# KEY_Pad.net
KiCad netlist of a schematic drawn in Altium Designer
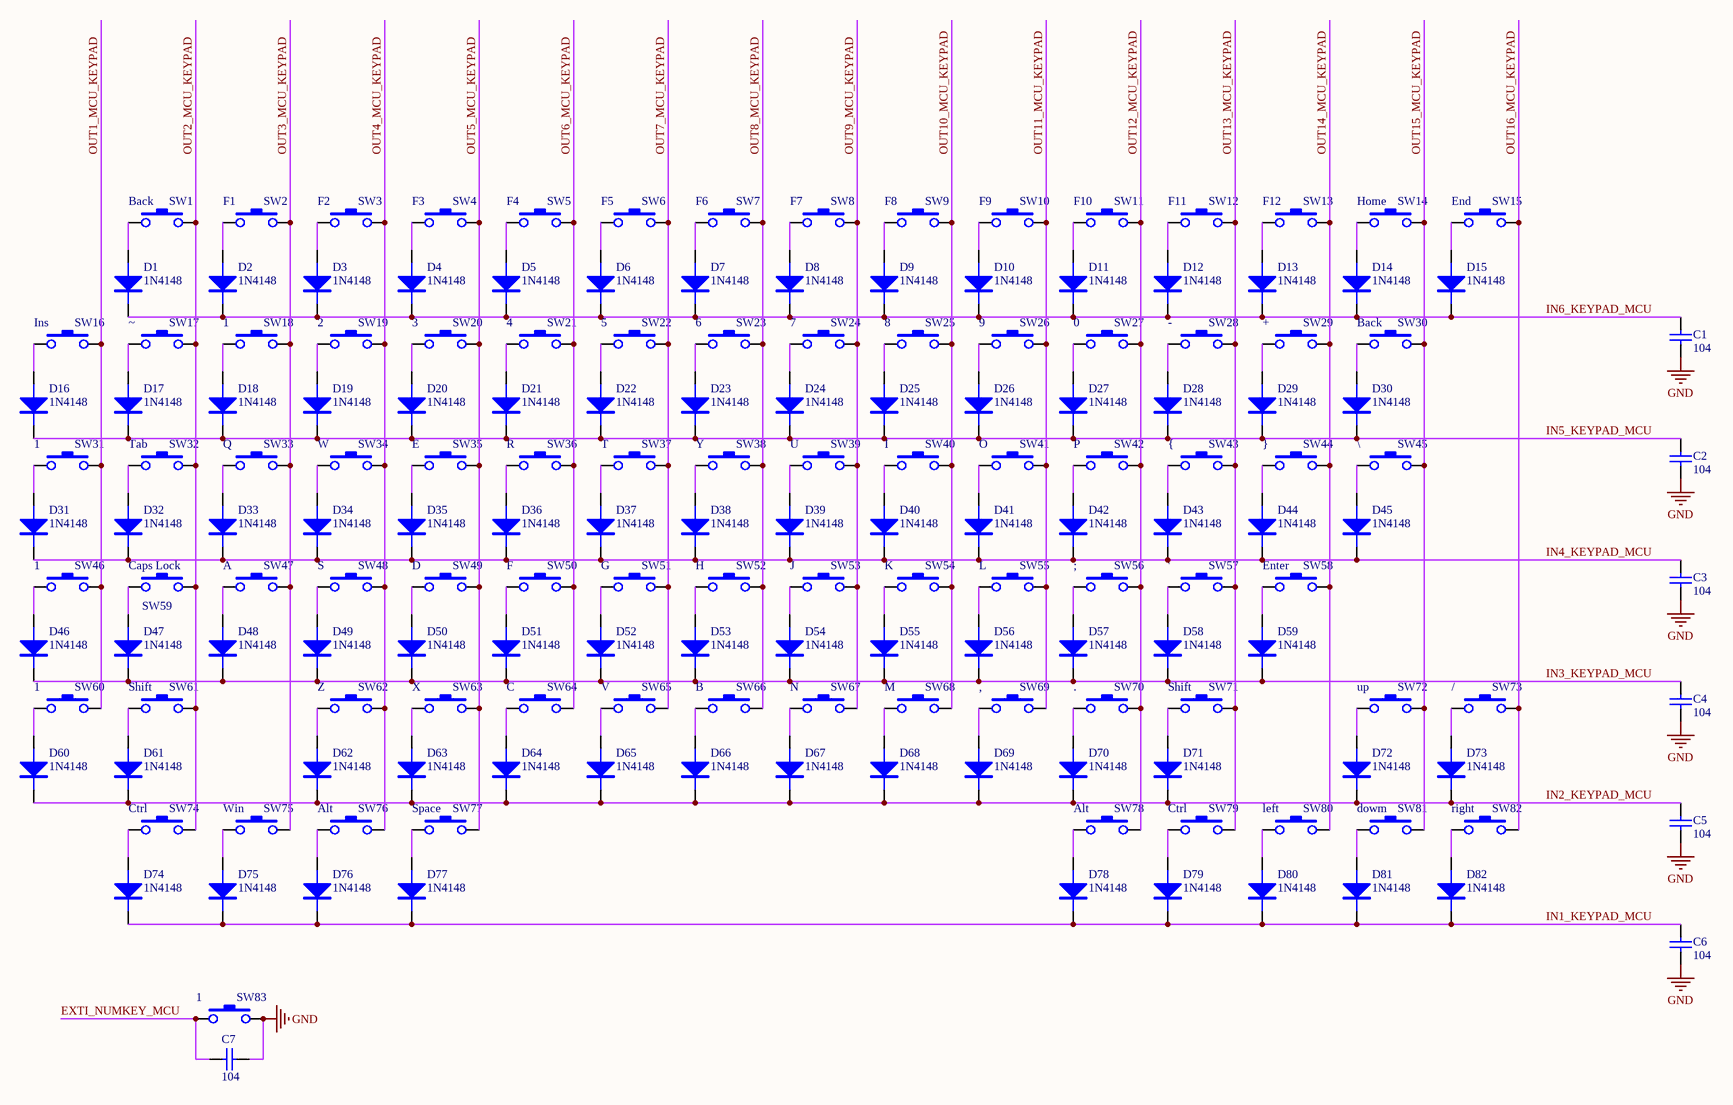
[diagram p0: KEY_Pad.SchDoc]

(export (version "E")
  (design (tool "Eeschema 10.0.6"))
  (components
    (comp (ref "C1")
      (value "104")
      (footprint "Cap-0603")
      (description "贴片陶瓷电容")
      (libsource (lib "Miscellaneous Base") (part "CAP"))
    )
    (comp (ref "C2")
      (value "104")
      (footprint "Cap-0603")
      (description "贴片陶瓷电容")
      (libsource (lib "Miscellaneous Base") (part "CAP"))
    )
    (comp (ref "C3")
      (value "104")
      (footprint "Cap-0603")
      (description "贴片陶瓷电容")
      (libsource (lib "Miscellaneous Base") (part "CAP"))
    )
    (comp (ref "C4")
      (value "104")
      (footprint "Cap-0603")
      (description "贴片陶瓷电容")
      (libsource (lib "Miscellaneous Base") (part "CAP"))
    )
    (comp (ref "C5")
      (value "104")
      (footprint "Cap-0603")
      (description "贴片陶瓷电容")
      (libsource (lib "Miscellaneous Base") (part "CAP"))
    )
    (comp (ref "C6")
      (value "104")
      (footprint "Cap-0603")
      (description "贴片陶瓷电容")
      (libsource (lib "Miscellaneous Base") (part "CAP"))
    )
    (comp (ref "C7")
      (value "104")
      (footprint "Cap-0603")
      (description "贴片陶瓷电容")
      (libsource (lib "Miscellaneous Base") (part "CAP"))
    )
    (comp (ref "D1")
      (value "1N4148")
      (footprint "SOD-523")
      (description "普通二极管")
      (libsource (lib "Miscellaneous Transistor") (part "DIODE"))
    )
    (comp (ref "D2")
      (value "1N4148")
      (footprint "SOD-523")
      (description "普通二极管")
      (libsource (lib "Miscellaneous Transistor") (part "DIODE"))
    )
    (comp (ref "D3")
      (value "1N4148")
      (footprint "SOD-523")
      (description "普通二极管")
      (libsource (lib "Miscellaneous Transistor") (part "DIODE"))
    )
    (comp (ref "D4")
      (value "1N4148")
      (footprint "SOD-523")
      (description "普通二极管")
      (libsource (lib "Miscellaneous Transistor") (part "DIODE"))
    )
    (comp (ref "D5")
      (value "1N4148")
      (footprint "SOD-523")
      (description "普通二极管")
      (libsource (lib "Miscellaneous Transistor") (part "DIODE"))
    )
    (comp (ref "D6")
      (value "1N4148")
      (footprint "SOD-523")
      (description "普通二极管")
      (libsource (lib "Miscellaneous Transistor") (part "DIODE"))
    )
    (comp (ref "D7")
      (value "1N4148")
      (footprint "SOD-523")
      (description "普通二极管")
      (libsource (lib "Miscellaneous Transistor") (part "DIODE"))
    )
    (comp (ref "D8")
      (value "1N4148")
      (footprint "SOD-523")
      (description "普通二极管")
      (libsource (lib "Miscellaneous Transistor") (part "DIODE"))
    )
    (comp (ref "D9")
      (value "1N4148")
      (footprint "SOD-523")
      (description "普通二极管")
      (libsource (lib "Miscellaneous Transistor") (part "DIODE"))
    )
    (comp (ref "D10")
      (value "1N4148")
      (footprint "SOD-523")
      (description "普通二极管")
      (libsource (lib "Miscellaneous Transistor") (part "DIODE"))
    )
    (comp (ref "D11")
      (value "1N4148")
      (footprint "SOD-523")
      (description "普通二极管")
      (libsource (lib "Miscellaneous Transistor") (part "DIODE"))
    )
    (comp (ref "D12")
      (value "1N4148")
      (footprint "SOD-523")
      (description "普通二极管")
      (libsource (lib "Miscellaneous Transistor") (part "DIODE"))
    )
    (comp (ref "D13")
      (value "1N4148")
      (footprint "SOD-523")
      (description "普通二极管")
      (libsource (lib "Miscellaneous Transistor") (part "DIODE"))
    )
    (comp (ref "D14")
      (value "1N4148")
      (footprint "SOD-523")
      (description "普通二极管")
      (libsource (lib "Miscellaneous Transistor") (part "DIODE"))
    )
    (comp (ref "D15")
      (value "1N4148")
      (footprint "SOD-523")
      (description "普通二极管")
      (libsource (lib "Miscellaneous Transistor") (part "DIODE"))
    )
    (comp (ref "D16")
      (value "1N4148")
      (footprint "SOD-523")
      (description "普通二极管")
      (libsource (lib "Miscellaneous Transistor") (part "DIODE"))
    )
    (comp (ref "D17")
      (value "1N4148")
      (footprint "SOD-523")
      (description "普通二极管")
      (libsource (lib "Miscellaneous Transistor") (part "DIODE"))
    )
    (comp (ref "D18")
      (value "1N4148")
      (footprint "SOD-523")
      (description "普通二极管")
      (libsource (lib "Miscellaneous Transistor") (part "DIODE"))
    )
    (comp (ref "D19")
      (value "1N4148")
      (footprint "SOD-523")
      (description "普通二极管")
      (libsource (lib "Miscellaneous Transistor") (part "DIODE"))
    )
    (comp (ref "D20")
      (value "1N4148")
      (footprint "SOD-523")
      (description "普通二极管")
      (libsource (lib "Miscellaneous Transistor") (part "DIODE"))
    )
    (comp (ref "D21")
      (value "1N4148")
      (footprint "SOD-523")
      (description "普通二极管")
      (libsource (lib "Miscellaneous Transistor") (part "DIODE"))
    )
    (comp (ref "D22")
      (value "1N4148")
      (footprint "SOD-523")
      (description "普通二极管")
      (libsource (lib "Miscellaneous Transistor") (part "DIODE"))
    )
    (comp (ref "D23")
      (value "1N4148")
      (footprint "SOD-523")
      (description "普通二极管")
      (libsource (lib "Miscellaneous Transistor") (part "DIODE"))
    )
    (comp (ref "D24")
      (value "1N4148")
      (footprint "SOD-523")
      (description "普通二极管")
      (libsource (lib "Miscellaneous Transistor") (part "DIODE"))
    )
    (comp (ref "D25")
      (value "1N4148")
      (footprint "SOD-523")
      (description "普通二极管")
      (libsource (lib "Miscellaneous Transistor") (part "DIODE"))
    )
    (comp (ref "D26")
      (value "1N4148")
      (footprint "SOD-523")
      (description "普通二极管")
      (libsource (lib "Miscellaneous Transistor") (part "DIODE"))
    )
    (comp (ref "D27")
      (value "1N4148")
      (footprint "SOD-523")
      (description "普通二极管")
      (libsource (lib "Miscellaneous Transistor") (part "DIODE"))
    )
    (comp (ref "D28")
      (value "1N4148")
      (footprint "SOD-523")
      (description "普通二极管")
      (libsource (lib "Miscellaneous Transistor") (part "DIODE"))
    )
    (comp (ref "D29")
      (value "1N4148")
      (footprint "SOD-523")
      (description "普通二极管")
      (libsource (lib "Miscellaneous Transistor") (part "DIODE"))
    )
    (comp (ref "D30")
      (value "1N4148")
      (footprint "SOD-523")
      (description "普通二极管")
      (libsource (lib "Miscellaneous Transistor") (part "DIODE"))
    )
    (comp (ref "D31")
      (value "1N4148")
      (footprint "SOD-523")
      (description "普通二极管")
      (libsource (lib "Miscellaneous Transistor") (part "DIODE"))
    )
    (comp (ref "D32")
      (value "1N4148")
      (footprint "SOD-523")
      (description "普通二极管")
      (libsource (lib "Miscellaneous Transistor") (part "DIODE"))
    )
    (comp (ref "D33")
      (value "1N4148")
      (footprint "SOD-523")
      (description "普通二极管")
      (libsource (lib "Miscellaneous Transistor") (part "DIODE"))
    )
    (comp (ref "D34")
      (value "1N4148")
      (footprint "SOD-523")
      (description "普通二极管")
      (libsource (lib "Miscellaneous Transistor") (part "DIODE"))
    )
    (comp (ref "D35")
      (value "1N4148")
      (footprint "SOD-523")
      (description "普通二极管")
      (libsource (lib "Miscellaneous Transistor") (part "DIODE"))
    )
    (comp (ref "D36")
      (value "1N4148")
      (footprint "SOD-523")
      (description "普通二极管")
      (libsource (lib "Miscellaneous Transistor") (part "DIODE"))
    )
    (comp (ref "D37")
      (value "1N4148")
      (footprint "SOD-523")
      (description "普通二极管")
      (libsource (lib "Miscellaneous Transistor") (part "DIODE"))
    )
    (comp (ref "D38")
      (value "1N4148")
      (footprint "SOD-523")
      (description "普通二极管")
      (libsource (lib "Miscellaneous Transistor") (part "DIODE"))
    )
    (comp (ref "D39")
      (value "1N4148")
      (footprint "SOD-523")
      (description "普通二极管")
      (libsource (lib "Miscellaneous Transistor") (part "DIODE"))
    )
    (comp (ref "D40")
      (value "1N4148")
      (footprint "SOD-523")
      (description "普通二极管")
      (libsource (lib "Miscellaneous Transistor") (part "DIODE"))
    )
    (comp (ref "D41")
      (value "1N4148")
      (footprint "SOD-523")
      (description "普通二极管")
      (libsource (lib "Miscellaneous Transistor") (part "DIODE"))
    )
    (comp (ref "D42")
      (value "1N4148")
      (footprint "SOD-523")
      (description "普通二极管")
      (libsource (lib "Miscellaneous Transistor") (part "DIODE"))
    )
    (comp (ref "D43")
      (value "1N4148")
      (footprint "SOD-523")
      (description "普通二极管")
      (libsource (lib "Miscellaneous Transistor") (part "DIODE"))
    )
    (comp (ref "D44")
      (value "1N4148")
      (footprint "SOD-523")
      (description "普通二极管")
      (libsource (lib "Miscellaneous Transistor") (part "DIODE"))
    )
    (comp (ref "D45")
      (value "1N4148")
      (footprint "SOD-523")
      (description "普通二极管")
      (libsource (lib "Miscellaneous Transistor") (part "DIODE"))
    )
    (comp (ref "D46")
      (value "1N4148")
      (footprint "SOD-523")
      (description "普通二极管")
      (libsource (lib "Miscellaneous Transistor") (part "DIODE"))
    )
    (comp (ref "D47")
      (value "1N4148")
      (footprint "SOD-523")
      (description "普通二极管")
      (libsource (lib "Miscellaneous Transistor") (part "DIODE"))
    )
    (comp (ref "D48")
      (value "1N4148")
      (footprint "SOD-523")
      (description "普通二极管")
      (libsource (lib "Miscellaneous Transistor") (part "DIODE"))
    )
    (comp (ref "D49")
      (value "1N4148")
      (footprint "SOD-523")
      (description "普通二极管")
      (libsource (lib "Miscellaneous Transistor") (part "DIODE"))
    )
    (comp (ref "D50")
      (value "1N4148")
      (footprint "SOD-523")
      (description "普通二极管")
      (libsource (lib "Miscellaneous Transistor") (part "DIODE"))
    )
    (comp (ref "D51")
      (value "1N4148")
      (footprint "SOD-523")
      (description "普通二极管")
      (libsource (lib "Miscellaneous Transistor") (part "DIODE"))
    )
    (comp (ref "D52")
      (value "1N4148")
      (footprint "SOD-523")
      (description "普通二极管")
      (libsource (lib "Miscellaneous Transistor") (part "DIODE"))
    )
    (comp (ref "D53")
      (value "1N4148")
      (footprint "SOD-523")
      (description "普通二极管")
      (libsource (lib "Miscellaneous Transistor") (part "DIODE"))
    )
    (comp (ref "D54")
      (value "1N4148")
      (footprint "SOD-523")
      (description "普通二极管")
      (libsource (lib "Miscellaneous Transistor") (part "DIODE"))
    )
    (comp (ref "D55")
      (value "1N4148")
      (footprint "SOD-523")
      (description "普通二极管")
      (libsource (lib "Miscellaneous Transistor") (part "DIODE"))
    )
    (comp (ref "D56")
      (value "1N4148")
      (footprint "SOD-523")
      (description "普通二极管")
      (libsource (lib "Miscellaneous Transistor") (part "DIODE"))
    )
    (comp (ref "D57")
      (value "1N4148")
      (footprint "SOD-523")
      (description "普通二极管")
      (libsource (lib "Miscellaneous Transistor") (part "DIODE"))
    )
    (comp (ref "D58")
      (value "1N4148")
      (footprint "SOD-523")
      (description "普通二极管")
      (libsource (lib "Miscellaneous Transistor") (part "DIODE"))
    )
    (comp (ref "D59")
      (value "1N4148")
      (footprint "SOD-523")
      (description "普通二极管")
      (libsource (lib "Miscellaneous Transistor") (part "DIODE"))
    )
    (comp (ref "D60")
      (value "1N4148")
      (footprint "SOD-523")
      (description "普通二极管")
      (libsource (lib "Miscellaneous Transistor") (part "DIODE"))
    )
    (comp (ref "D61")
      (value "1N4148")
      (footprint "SOD-523")
      (description "普通二极管")
      (libsource (lib "Miscellaneous Transistor") (part "DIODE"))
    )
    (comp (ref "D62")
      (value "1N4148")
      (footprint "SOD-523")
      (description "普通二极管")
      (libsource (lib "Miscellaneous Transistor") (part "DIODE"))
    )
    (comp (ref "D63")
      (value "1N4148")
      (footprint "SOD-523")
      (description "普通二极管")
      (libsource (lib "Miscellaneous Transistor") (part "DIODE"))
    )
    (comp (ref "D64")
      (value "1N4148")
      (footprint "SOD-523")
      (description "普通二极管")
      (libsource (lib "Miscellaneous Transistor") (part "DIODE"))
    )
    (comp (ref "D65")
      (value "1N4148")
      (footprint "SOD-523")
      (description "普通二极管")
      (libsource (lib "Miscellaneous Transistor") (part "DIODE"))
    )
    (comp (ref "D66")
      (value "1N4148")
      (footprint "SOD-523")
      (description "普通二极管")
      (libsource (lib "Miscellaneous Transistor") (part "DIODE"))
    )
    (comp (ref "D67")
      (value "1N4148")
      (footprint "SOD-523")
      (description "普通二极管")
      (libsource (lib "Miscellaneous Transistor") (part "DIODE"))
    )
    (comp (ref "D68")
      (value "1N4148")
      (footprint "SOD-523")
      (description "普通二极管")
      (libsource (lib "Miscellaneous Transistor") (part "DIODE"))
    )
    (comp (ref "D69")
      (value "1N4148")
      (footprint "SOD-523")
      (description "普通二极管")
      (libsource (lib "Miscellaneous Transistor") (part "DIODE"))
    )
    (comp (ref "D70")
      (value "1N4148")
      (footprint "SOD-523")
      (description "普通二极管")
      (libsource (lib "Miscellaneous Transistor") (part "DIODE"))
    )
    (comp (ref "D71")
      (value "1N4148")
      (footprint "SOD-523")
      (description "普通二极管")
      (libsource (lib "Miscellaneous Transistor") (part "DIODE"))
    )
    (comp (ref "D72")
      (value "1N4148")
      (footprint "SOD-523")
      (description "普通二极管")
      (libsource (lib "Miscellaneous Transistor") (part "DIODE"))
    )
    (comp (ref "D73")
      (value "1N4148")
      (footprint "SOD-523")
      (description "普通二极管")
      (libsource (lib "Miscellaneous Transistor") (part "DIODE"))
    )
    (comp (ref "D74")
      (value "1N4148")
      (footprint "SOD-523")
      (description "普通二极管")
      (libsource (lib "Miscellaneous Transistor") (part "DIODE"))
    )
    (comp (ref "D75")
      (value "1N4148")
      (footprint "SOD-523")
      (description "普通二极管")
      (libsource (lib "Miscellaneous Transistor") (part "DIODE"))
    )
    (comp (ref "D76")
      (value "1N4148")
      (footprint "SOD-523")
      (description "普通二极管")
      (libsource (lib "Miscellaneous Transistor") (part "DIODE"))
    )
    (comp (ref "D77")
      (value "1N4148")
      (footprint "SOD-523")
      (description "普通二极管")
      (libsource (lib "Miscellaneous Transistor") (part "DIODE"))
    )
    (comp (ref "D78")
      (value "1N4148")
      (footprint "SOD-523")
      (description "普通二极管")
      (libsource (lib "Miscellaneous Transistor") (part "DIODE"))
    )
    (comp (ref "D79")
      (value "1N4148")
      (footprint "SOD-523")
      (description "普通二极管")
      (libsource (lib "Miscellaneous Transistor") (part "DIODE"))
    )
    (comp (ref "D80")
      (value "1N4148")
      (footprint "SOD-523")
      (description "普通二极管")
      (libsource (lib "Miscellaneous Transistor") (part "DIODE"))
    )
    (comp (ref "D81")
      (value "1N4148")
      (footprint "SOD-523")
      (description "普通二极管")
      (libsource (lib "Miscellaneous Transistor") (part "DIODE"))
    )
    (comp (ref "D82")
      (value "1N4148")
      (footprint "SOD-523")
      (description "普通二极管")
      (libsource (lib "Miscellaneous Transistor") (part "DIODE"))
    )
    (comp (ref "SW1")
      (value "Back")
      (footprint "MX_SW-4")
      (description "with Fixation pins  1-Pole")
      (libsource (lib "KeyBoard_rebacha") (part "MX_SW-4"))
    )
    (comp (ref "SW2")
      (value "F1")
      (footprint "MX_SW-4")
      (description "with Fixation pins  1-Pole")
      (libsource (lib "KeyBoard_rebacha") (part "MX_SW-4"))
    )
    (comp (ref "SW3")
      (value "F2")
      (footprint "MX_SW-4")
      (description "with Fixation pins  1-Pole")
      (libsource (lib "KeyBoard_rebacha") (part "MX_SW-4"))
    )
    (comp (ref "SW4")
      (value "F3")
      (footprint "MX_SW-4")
      (description "with Fixation pins  1-Pole")
      (libsource (lib "KeyBoard_rebacha") (part "MX_SW-4"))
    )
    (comp (ref "SW5")
      (value "F4")
      (footprint "MX_SW-4")
      (description "with Fixation pins  1-Pole")
      (libsource (lib "KeyBoard_rebacha") (part "MX_SW-4"))
    )
    (comp (ref "SW6")
      (value "F5")
      (footprint "MX_SW-4")
      (description "with Fixation pins  1-Pole")
      (libsource (lib "KeyBoard_rebacha") (part "MX_SW-4"))
    )
    (comp (ref "SW7")
      (value "F6")
      (footprint "MX_SW-4")
      (description "with Fixation pins  1-Pole")
      (libsource (lib "KeyBoard_rebacha") (part "MX_SW-4"))
    )
    (comp (ref "SW8")
      (value "F7")
      (footprint "MX_SW-4")
      (description "with Fixation pins  1-Pole")
      (libsource (lib "KeyBoard_rebacha") (part "MX_SW-4"))
    )
    (comp (ref "SW9")
      (value "F8")
      (footprint "MX_SW-4")
      (description "with Fixation pins  1-Pole")
      (libsource (lib "KeyBoard_rebacha") (part "MX_SW-4"))
    )
    (comp (ref "SW10")
      (value "F9")
      (footprint "MX_SW-4")
      (description "with Fixation pins  1-Pole")
      (libsource (lib "KeyBoard_rebacha") (part "MX_SW-4"))
    )
    (comp (ref "SW11")
      (value "F10")
      (footprint "MX_SW-4")
      (description "with Fixation pins  1-Pole")
      (libsource (lib "KeyBoard_rebacha") (part "MX_SW-4"))
    )
    (comp (ref "SW12")
      (value "F11")
      (footprint "MX_SW-4")
      (description "with Fixation pins  1-Pole")
      (libsource (lib "KeyBoard_rebacha") (part "MX_SW-4"))
    )
    (comp (ref "SW13")
      (value "F12")
      (footprint "MX_SW-4")
      (description "with Fixation pins  1-Pole")
      (libsource (lib "KeyBoard_rebacha") (part "MX_SW-4"))
    )
    (comp (ref "SW14")
      (value "Home")
      (footprint "MX_SW-4")
      (description "with Fixation pins  1-Pole")
      (libsource (lib "KeyBoard_rebacha") (part "MX_SW-4"))
    )
    (comp (ref "SW15")
      (value "End")
      (footprint "MX_SW-4")
      (description "with Fixation pins  1-Pole")
      (libsource (lib "KeyBoard_rebacha") (part "MX_SW-4"))
    )
    (comp (ref "SW16")
      (value "Ins")
      (footprint "MX_SW-4")
      (description "with Fixation pins  1-Pole")
      (libsource (lib "KeyBoard_rebacha") (part "MX_SW-4"))
    )
    (comp (ref "SW17")
      (value "~")
      (footprint "MX_SW-4")
      (description "with Fixation pins  1-Pole")
      (libsource (lib "KeyBoard_rebacha") (part "MX_SW-4"))
    )
    (comp (ref "SW18")
      (value "1")
      (footprint "MX_SW-4")
      (description "with Fixation pins  1-Pole")
      (libsource (lib "KeyBoard_rebacha") (part "MX_SW-4"))
    )
    (comp (ref "SW19")
      (value "2")
      (footprint "MX_SW-4")
      (description "with Fixation pins  1-Pole")
      (libsource (lib "KeyBoard_rebacha") (part "MX_SW-4"))
    )
    (comp (ref "SW20")
      (value "3")
      (footprint "MX_SW-4")
      (description "with Fixation pins  1-Pole")
      (libsource (lib "KeyBoard_rebacha") (part "MX_SW-4"))
    )
    (comp (ref "SW21")
      (value "4")
      (footprint "MX_SW-4")
      (description "with Fixation pins  1-Pole")
      (libsource (lib "KeyBoard_rebacha") (part "MX_SW-4"))
    )
    (comp (ref "SW22")
      (value "5")
      (footprint "MX_SW-4")
      (description "with Fixation pins  1-Pole")
      (libsource (lib "KeyBoard_rebacha") (part "MX_SW-4"))
    )
    (comp (ref "SW23")
      (value "6")
      (footprint "MX_SW-4")
      (description "with Fixation pins  1-Pole")
      (libsource (lib "KeyBoard_rebacha") (part "MX_SW-4"))
    )
    (comp (ref "SW24")
      (value "7")
      (footprint "MX_SW-4")
      (description "with Fixation pins  1-Pole")
      (libsource (lib "KeyBoard_rebacha") (part "MX_SW-4"))
    )
    (comp (ref "SW25")
      (value "8")
      (footprint "MX_SW-4")
      (description "with Fixation pins  1-Pole")
      (libsource (lib "KeyBoard_rebacha") (part "MX_SW-4"))
    )
    (comp (ref "SW26")
      (value "9")
      (footprint "MX_SW-4")
      (description "with Fixation pins  1-Pole")
      (libsource (lib "KeyBoard_rebacha") (part "MX_SW-4"))
    )
    (comp (ref "SW27")
      (value "0")
      (footprint "MX_SW-4")
      (description "with Fixation pins  1-Pole")
      (libsource (lib "KeyBoard_rebacha") (part "MX_SW-4"))
    )
    (comp (ref "SW28")
      (value "-")
      (footprint "MX_SW-4")
      (description "with Fixation pins  1-Pole")
      (libsource (lib "KeyBoard_rebacha") (part "MX_SW-4"))
    )
    (comp (ref "SW29")
      (value "+")
      (footprint "MX_SW-4")
      (description "with Fixation pins  1-Pole")
      (libsource (lib "KeyBoard_rebacha") (part "MX_SW-4"))
    )
    (comp (ref "SW30")
      (value "Back")
      (footprint "MX_SW-4")
      (description "with Fixation pins  1-Pole")
      (libsource (lib "KeyBoard_rebacha") (part "MX_SW-4"))
    )
    (comp (ref "SW31")
      (value "1")
      (footprint "MX_SW-4")
      (description "with Fixation pins  1-Pole")
      (libsource (lib "KeyBoard_rebacha") (part "MX_SW-4"))
    )
    (comp (ref "SW32")
      (value "Tab")
      (footprint "MX_SW-4")
      (description "with Fixation pins  1-Pole")
      (libsource (lib "KeyBoard_rebacha") (part "MX_SW-4"))
    )
    (comp (ref "SW33")
      (value "Q")
      (footprint "MX_SW-4")
      (description "with Fixation pins  1-Pole")
      (libsource (lib "KeyBoard_rebacha") (part "MX_SW-4"))
    )
    (comp (ref "SW34")
      (value "W")
      (footprint "MX_SW-4")
      (description "with Fixation pins  1-Pole")
      (libsource (lib "KeyBoard_rebacha") (part "MX_SW-4"))
    )
    (comp (ref "SW35")
      (value "E")
      (footprint "MX_SW-4")
      (description "with Fixation pins  1-Pole")
      (libsource (lib "KeyBoard_rebacha") (part "MX_SW-4"))
    )
    (comp (ref "SW36")
      (value "R")
      (footprint "MX_SW-4")
      (description "with Fixation pins  1-Pole")
      (libsource (lib "KeyBoard_rebacha") (part "MX_SW-4"))
    )
    (comp (ref "SW37")
      (value "T")
      (footprint "MX_SW-4")
      (description "with Fixation pins  1-Pole")
      (libsource (lib "KeyBoard_rebacha") (part "MX_SW-4"))
    )
    (comp (ref "SW38")
      (value "Y")
      (footprint "MX_SW-4")
      (description "with Fixation pins  1-Pole")
      (libsource (lib "KeyBoard_rebacha") (part "MX_SW-4"))
    )
    (comp (ref "SW39")
      (value "U")
      (footprint "MX_SW-4")
      (description "with Fixation pins  1-Pole")
      (libsource (lib "KeyBoard_rebacha") (part "MX_SW-4"))
    )
    (comp (ref "SW40")
      (value "I")
      (footprint "MX_SW-4")
      (description "with Fixation pins  1-Pole")
      (libsource (lib "KeyBoard_rebacha") (part "MX_SW-4"))
    )
    (comp (ref "SW41")
      (value "O")
      (footprint "MX_SW-4")
      (description "with Fixation pins  1-Pole")
      (libsource (lib "KeyBoard_rebacha") (part "MX_SW-4"))
    )
    (comp (ref "SW42")
      (value "P")
      (footprint "MX_SW-4")
      (description "with Fixation pins  1-Pole")
      (libsource (lib "KeyBoard_rebacha") (part "MX_SW-4"))
    )
    (comp (ref "SW43")
      (value "{")
      (footprint "MX_SW-4")
      (description "with Fixation pins  1-Pole")
      (libsource (lib "KeyBoard_rebacha") (part "MX_SW-4"))
    )
    (comp (ref "SW44")
      (value "}")
      (footprint "MX_SW-4")
      (description "with Fixation pins  1-Pole")
      (libsource (lib "KeyBoard_rebacha") (part "MX_SW-4"))
    )
    (comp (ref "SW45")
      (value "~")
      (footprint "MX_SW-4")
      (description "with Fixation pins  1-Pole")
      (libsource (lib "KeyBoard_rebacha") (part "MX_SW-4"))
    )
    (comp (ref "SW46")
      (value "1")
      (footprint "MX_SW-4")
      (description "with Fixation pins  1-Pole")
      (libsource (lib "KeyBoard_rebacha") (part "MX_SW-4"))
    )
    (comp (ref "SW47")
      (value "A")
      (footprint "MX_SW-4")
      (description "with Fixation pins  1-Pole")
      (libsource (lib "KeyBoard_rebacha") (part "MX_SW-4"))
    )
    (comp (ref "SW48")
      (value "S")
      (footprint "MX_SW-4")
      (description "with Fixation pins  1-Pole")
      (libsource (lib "KeyBoard_rebacha") (part "MX_SW-4"))
    )
    (comp (ref "SW49")
      (value "D")
      (footprint "MX_SW-4")
      (description "with Fixation pins  1-Pole")
      (libsource (lib "KeyBoard_rebacha") (part "MX_SW-4"))
    )
    (comp (ref "SW50")
      (value "F")
      (footprint "MX_SW-4")
      (description "with Fixation pins  1-Pole")
      (libsource (lib "KeyBoard_rebacha") (part "MX_SW-4"))
    )
    (comp (ref "SW51")
      (value "G")
      (footprint "MX_SW-4")
      (description "with Fixation pins  1-Pole")
      (libsource (lib "KeyBoard_rebacha") (part "MX_SW-4"))
    )
    (comp (ref "SW52")
      (value "H")
      (footprint "MX_SW-4")
      (description "with Fixation pins  1-Pole")
      (libsource (lib "KeyBoard_rebacha") (part "MX_SW-4"))
    )
    (comp (ref "SW53")
      (value "J")
      (footprint "MX_SW-4")
      (description "with Fixation pins  1-Pole")
      (libsource (lib "KeyBoard_rebacha") (part "MX_SW-4"))
    )
    (comp (ref "SW54")
      (value "K")
      (footprint "MX_SW-4")
      (description "with Fixation pins  1-Pole")
      (libsource (lib "KeyBoard_rebacha") (part "MX_SW-4"))
    )
    (comp (ref "SW55")
      (value "L")
      (footprint "MX_SW-4")
      (description "with Fixation pins  1-Pole")
      (libsource (lib "KeyBoard_rebacha") (part "MX_SW-4"))
    )
    (comp (ref "SW56")
      (value ";")
      (footprint "MX_SW-4")
      (description "with Fixation pins  1-Pole")
      (libsource (lib "KeyBoard_rebacha") (part "MX_SW-4"))
    )
    (comp (ref "SW57")
      (value "'")
      (footprint "MX_SW-4")
      (description "with Fixation pins  1-Pole")
      (libsource (lib "KeyBoard_rebacha") (part "MX_SW-4"))
    )
    (comp (ref "SW58")
      (value "Enter")
      (footprint "MX_SW-4")
      (description "with Fixation pins  1-Pole")
      (libsource (lib "KeyBoard_rebacha") (part "MX_SW-4"))
    )
    (comp (ref "SW59")
      (value "Caps Lock")
      (footprint "MX_SW-4")
      (description "with Fixation pins  1-Pole")
      (libsource (lib "KeyBoard_rebacha") (part "MX_SW-4"))
    )
    (comp (ref "SW60")
      (value "1")
      (footprint "MX_SW-4")
      (description "with Fixation pins  1-Pole")
      (libsource (lib "KeyBoard_rebacha") (part "MX_SW-4"))
    )
    (comp (ref "SW61")
      (value "Shift")
      (footprint "MX_SW-4")
      (description "with Fixation pins  1-Pole")
      (libsource (lib "KeyBoard_rebacha") (part "MX_SW-4"))
    )
    (comp (ref "SW62")
      (value "Z")
      (footprint "MX_SW-4")
      (description "with Fixation pins  1-Pole")
      (libsource (lib "KeyBoard_rebacha") (part "MX_SW-4"))
    )
    (comp (ref "SW63")
      (value "X")
      (footprint "MX_SW-4")
      (description "with Fixation pins  1-Pole")
      (libsource (lib "KeyBoard_rebacha") (part "MX_SW-4"))
    )
    (comp (ref "SW64")
      (value "C")
      (footprint "MX_SW-4")
      (description "with Fixation pins  1-Pole")
      (libsource (lib "KeyBoard_rebacha") (part "MX_SW-4"))
    )
    (comp (ref "SW65")
      (value "V")
      (footprint "MX_SW-4")
      (description "with Fixation pins  1-Pole")
      (libsource (lib "KeyBoard_rebacha") (part "MX_SW-4"))
    )
    (comp (ref "SW66")
      (value "B")
      (footprint "MX_SW-4")
      (description "with Fixation pins  1-Pole")
      (libsource (lib "KeyBoard_rebacha") (part "MX_SW-4"))
    )
    (comp (ref "SW67")
      (value "N")
      (footprint "MX_SW-4")
      (description "with Fixation pins  1-Pole")
      (libsource (lib "KeyBoard_rebacha") (part "MX_SW-4"))
    )
    (comp (ref "SW68")
      (value "M")
      (footprint "MX_SW-4")
      (description "with Fixation pins  1-Pole")
      (libsource (lib "KeyBoard_rebacha") (part "MX_SW-4"))
    )
    (comp (ref "SW69")
      (value ",")
      (footprint "MX_SW-4")
      (description "with Fixation pins  1-Pole")
      (libsource (lib "KeyBoard_rebacha") (part "MX_SW-4"))
    )
    (comp (ref "SW70")
      (value ".")
      (footprint "MX_SW-4")
      (description "with Fixation pins  1-Pole")
      (libsource (lib "KeyBoard_rebacha") (part "MX_SW-4"))
    )
    (comp (ref "SW71")
      (value "Shift")
      (footprint "MX_SW-4")
      (description "with Fixation pins  1-Pole")
      (libsource (lib "KeyBoard_rebacha") (part "MX_SW-4"))
    )
    (comp (ref "SW72")
      (value "up")
      (footprint "MX_SW-4")
      (description "with Fixation pins  1-Pole")
      (libsource (lib "KeyBoard_rebacha") (part "MX_SW-4"))
    )
    (comp (ref "SW73")
      (value "/")
      (footprint "MX_SW-4")
      (description "with Fixation pins  1-Pole")
      (libsource (lib "KeyBoard_rebacha") (part "MX_SW-4"))
    )
    (comp (ref "SW74")
      (value "Ctrl")
      (footprint "MX_SW-4")
      (description "with Fixation pins  1-Pole")
      (libsource (lib "KeyBoard_rebacha") (part "MX_SW-4"))
    )
    (comp (ref "SW75")
      (value "Win")
      (footprint "MX_SW-4")
      (description "with Fixation pins  1-Pole")
      (libsource (lib "KeyBoard_rebacha") (part "MX_SW-4"))
    )
    (comp (ref "SW76")
      (value "Alt")
      (footprint "MX_SW-4")
      (description "with Fixation pins  1-Pole")
      (libsource (lib "KeyBoard_rebacha") (part "MX_SW-4"))
    )
    (comp (ref "SW77")
      (value "Space")
      (footprint "MX_SW-4")
      (description "with Fixation pins  1-Pole")
      (libsource (lib "KeyBoard_rebacha") (part "MX_SW-4"))
    )
    (comp (ref "SW78")
      (value "Alt")
      (footprint "MX_SW-4")
      (description "with Fixation pins  1-Pole")
      (libsource (lib "KeyBoard_rebacha") (part "MX_SW-4"))
    )
    (comp (ref "SW79")
      (value "Ctrl")
      (footprint "MX_SW-4")
      (description "with Fixation pins  1-Pole")
      (libsource (lib "KeyBoard_rebacha") (part "MX_SW-4"))
    )
    (comp (ref "SW80")
      (value "left")
      (footprint "MX_SW-4")
      (description "with Fixation pins  1-Pole")
      (libsource (lib "KeyBoard_rebacha") (part "MX_SW-4"))
    )
    (comp (ref "SW81")
      (value "dowm")
      (footprint "MX_SW-4")
      (description "with Fixation pins  1-Pole")
      (libsource (lib "KeyBoard_rebacha") (part "MX_SW-4"))
    )
    (comp (ref "SW82")
      (value "right")
      (footprint "MX_SW-4")
      (description "with Fixation pins  1-Pole")
      (libsource (lib "KeyBoard_rebacha") (part "MX_SW-4"))
    )
    (comp (ref "SW83")
      (value "1")
      (footprint "MX_SW-4")
      (description "with Fixation pins  1-Pole")
      (libsource (lib "KeyBoard_rebacha") (part "MX_SW-4"))
    )
  )
  (nets
    (net (code "1") (name "/EXTI_NUMKEY_MCU") (class "Default")
      (node (ref "C7") (pin "1") (pinfunction "1_1") (pintype "passive"))
      (node (ref "SW83") (pin "1") (pinfunction "1_1") (pintype "passive"))
    )
    (net (code "2") (name "/IN1_KEYPAD_MCU") (class "Default")
      (node (ref "C6") (pin "1") (pinfunction "1_1") (pintype "passive"))
      (node (ref "D74") (pin "K") (pinfunction "K_K") (pintype "passive"))
      (node (ref "D75") (pin "K") (pinfunction "K_K") (pintype "passive"))
      (node (ref "D76") (pin "K") (pinfunction "K_K") (pintype "passive"))
      (node (ref "D77") (pin "K") (pinfunction "K_K") (pintype "passive"))
      (node (ref "D78") (pin "K") (pinfunction "K_K") (pintype "passive"))
      (node (ref "D79") (pin "K") (pinfunction "K_K") (pintype "passive"))
      (node (ref "D80") (pin "K") (pinfunction "K_K") (pintype "passive"))
      (node (ref "D81") (pin "K") (pinfunction "K_K") (pintype "passive"))
      (node (ref "D82") (pin "K") (pinfunction "K_K") (pintype "passive"))
    )
    (net (code "3") (name "/IN2_KEYPAD_MCU") (class "Default")
      (node (ref "C5") (pin "1") (pinfunction "1_1") (pintype "passive"))
      (node (ref "D60") (pin "K") (pinfunction "K_K") (pintype "passive"))
      (node (ref "D61") (pin "K") (pinfunction "K_K") (pintype "passive"))
      (node (ref "D62") (pin "K") (pinfunction "K_K") (pintype "passive"))
      (node (ref "D63") (pin "K") (pinfunction "K_K") (pintype "passive"))
      (node (ref "D64") (pin "K") (pinfunction "K_K") (pintype "passive"))
      (node (ref "D65") (pin "K") (pinfunction "K_K") (pintype "passive"))
      (node (ref "D66") (pin "K") (pinfunction "K_K") (pintype "passive"))
      (node (ref "D67") (pin "K") (pinfunction "K_K") (pintype "passive"))
      (node (ref "D68") (pin "K") (pinfunction "K_K") (pintype "passive"))
      (node (ref "D69") (pin "K") (pinfunction "K_K") (pintype "passive"))
      (node (ref "D70") (pin "K") (pinfunction "K_K") (pintype "passive"))
      (node (ref "D71") (pin "K") (pinfunction "K_K") (pintype "passive"))
      (node (ref "D72") (pin "K") (pinfunction "K_K") (pintype "passive"))
      (node (ref "D73") (pin "K") (pinfunction "K_K") (pintype "passive"))
    )
    (net (code "4") (name "/IN3_KEYPAD_MCU") (class "Default")
      (node (ref "C4") (pin "1") (pinfunction "1_1") (pintype "passive"))
      (node (ref "D46") (pin "K") (pinfunction "K_K") (pintype "passive"))
      (node (ref "D47") (pin "K") (pinfunction "K_K") (pintype "passive"))
      (node (ref "D48") (pin "K") (pinfunction "K_K") (pintype "passive"))
      (node (ref "D49") (pin "K") (pinfunction "K_K") (pintype "passive"))
      (node (ref "D50") (pin "K") (pinfunction "K_K") (pintype "passive"))
      (node (ref "D51") (pin "K") (pinfunction "K_K") (pintype "passive"))
      (node (ref "D52") (pin "K") (pinfunction "K_K") (pintype "passive"))
      (node (ref "D53") (pin "K") (pinfunction "K_K") (pintype "passive"))
      (node (ref "D54") (pin "K") (pinfunction "K_K") (pintype "passive"))
      (node (ref "D55") (pin "K") (pinfunction "K_K") (pintype "passive"))
      (node (ref "D56") (pin "K") (pinfunction "K_K") (pintype "passive"))
      (node (ref "D57") (pin "K") (pinfunction "K_K") (pintype "passive"))
      (node (ref "D58") (pin "K") (pinfunction "K_K") (pintype "passive"))
      (node (ref "D59") (pin "K") (pinfunction "K_K") (pintype "passive"))
    )
    (net (code "5") (name "/IN4_KEYPAD_MCU") (class "Default")
      (node (ref "C3") (pin "1") (pinfunction "1_1") (pintype "passive"))
      (node (ref "D31") (pin "K") (pinfunction "K_K") (pintype "passive"))
      (node (ref "D32") (pin "K") (pinfunction "K_K") (pintype "passive"))
      (node (ref "D33") (pin "K") (pinfunction "K_K") (pintype "passive"))
      (node (ref "D34") (pin "K") (pinfunction "K_K") (pintype "passive"))
      (node (ref "D35") (pin "K") (pinfunction "K_K") (pintype "passive"))
      (node (ref "D36") (pin "K") (pinfunction "K_K") (pintype "passive"))
      (node (ref "D37") (pin "K") (pinfunction "K_K") (pintype "passive"))
      (node (ref "D38") (pin "K") (pinfunction "K_K") (pintype "passive"))
      (node (ref "D39") (pin "K") (pinfunction "K_K") (pintype "passive"))
      (node (ref "D40") (pin "K") (pinfunction "K_K") (pintype "passive"))
      (node (ref "D41") (pin "K") (pinfunction "K_K") (pintype "passive"))
      (node (ref "D42") (pin "K") (pinfunction "K_K") (pintype "passive"))
      (node (ref "D43") (pin "K") (pinfunction "K_K") (pintype "passive"))
      (node (ref "D44") (pin "K") (pinfunction "K_K") (pintype "passive"))
      (node (ref "D45") (pin "K") (pinfunction "K_K") (pintype "passive"))
    )
    (net (code "6") (name "/IN5_KEYPAD_MCU") (class "Default")
      (node (ref "C2") (pin "1") (pinfunction "1_1") (pintype "passive"))
      (node (ref "D16") (pin "K") (pinfunction "K_K") (pintype "passive"))
      (node (ref "D17") (pin "K") (pinfunction "K_K") (pintype "passive"))
      (node (ref "D18") (pin "K") (pinfunction "K_K") (pintype "passive"))
      (node (ref "D19") (pin "K") (pinfunction "K_K") (pintype "passive"))
      (node (ref "D20") (pin "K") (pinfunction "K_K") (pintype "passive"))
      (node (ref "D21") (pin "K") (pinfunction "K_K") (pintype "passive"))
      (node (ref "D22") (pin "K") (pinfunction "K_K") (pintype "passive"))
      (node (ref "D23") (pin "K") (pinfunction "K_K") (pintype "passive"))
      (node (ref "D24") (pin "K") (pinfunction "K_K") (pintype "passive"))
      (node (ref "D25") (pin "K") (pinfunction "K_K") (pintype "passive"))
      (node (ref "D26") (pin "K") (pinfunction "K_K") (pintype "passive"))
      (node (ref "D27") (pin "K") (pinfunction "K_K") (pintype "passive"))
      (node (ref "D28") (pin "K") (pinfunction "K_K") (pintype "passive"))
      (node (ref "D29") (pin "K") (pinfunction "K_K") (pintype "passive"))
      (node (ref "D30") (pin "K") (pinfunction "K_K") (pintype "passive"))
    )
    (net (code "7") (name "/IN6_KEYPAD_MCU") (class "Default")
      (node (ref "C1") (pin "1") (pinfunction "1_1") (pintype "passive"))
      (node (ref "D1") (pin "K") (pinfunction "K_K") (pintype "passive"))
      (node (ref "D10") (pin "K") (pinfunction "K_K") (pintype "passive"))
      (node (ref "D11") (pin "K") (pinfunction "K_K") (pintype "passive"))
      (node (ref "D12") (pin "K") (pinfunction "K_K") (pintype "passive"))
      (node (ref "D13") (pin "K") (pinfunction "K_K") (pintype "passive"))
      (node (ref "D14") (pin "K") (pinfunction "K_K") (pintype "passive"))
      (node (ref "D15") (pin "K") (pinfunction "K_K") (pintype "passive"))
      (node (ref "D2") (pin "K") (pinfunction "K_K") (pintype "passive"))
      (node (ref "D3") (pin "K") (pinfunction "K_K") (pintype "passive"))
      (node (ref "D4") (pin "K") (pinfunction "K_K") (pintype "passive"))
      (node (ref "D5") (pin "K") (pinfunction "K_K") (pintype "passive"))
      (node (ref "D6") (pin "K") (pinfunction "K_K") (pintype "passive"))
      (node (ref "D7") (pin "K") (pinfunction "K_K") (pintype "passive"))
      (node (ref "D8") (pin "K") (pinfunction "K_K") (pintype "passive"))
      (node (ref "D9") (pin "K") (pinfunction "K_K") (pintype "passive"))
    )
    (net (code "8") (name "/OUT1_MCU_KEYPAD") (class "Default")
      (node (ref "SW16") (pin "2") (pinfunction "2_2") (pintype "passive"))
      (node (ref "SW31") (pin "2") (pinfunction "2_2") (pintype "passive"))
      (node (ref "SW46") (pin "2") (pinfunction "2_2") (pintype "passive"))
      (node (ref "SW60") (pin "2") (pinfunction "2_2") (pintype "passive"))
    )
    (net (code "9") (name "/OUT2_MCU_KEYPAD") (class "Default")
      (node (ref "SW1") (pin "2") (pinfunction "2_2") (pintype "passive"))
      (node (ref "SW17") (pin "2") (pinfunction "2_2") (pintype "passive"))
      (node (ref "SW32") (pin "2") (pinfunction "2_2") (pintype "passive"))
      (node (ref "SW59") (pin "2") (pinfunction "2_2") (pintype "passive"))
      (node (ref "SW61") (pin "2") (pinfunction "2_2") (pintype "passive"))
      (node (ref "SW74") (pin "2") (pinfunction "2_2") (pintype "passive"))
    )
    (net (code "10") (name "/OUT3_MCU_KEYPAD") (class "Default")
      (node (ref "SW18") (pin "2") (pinfunction "2_2") (pintype "passive"))
      (node (ref "SW2") (pin "2") (pinfunction "2_2") (pintype "passive"))
      (node (ref "SW33") (pin "2") (pinfunction "2_2") (pintype "passive"))
      (node (ref "SW47") (pin "2") (pinfunction "2_2") (pintype "passive"))
      (node (ref "SW75") (pin "2") (pinfunction "2_2") (pintype "passive"))
    )
    (net (code "11") (name "/OUT4_MCU_KEYPAD") (class "Default")
      (node (ref "SW19") (pin "2") (pinfunction "2_2") (pintype "passive"))
      (node (ref "SW3") (pin "2") (pinfunction "2_2") (pintype "passive"))
      (node (ref "SW34") (pin "2") (pinfunction "2_2") (pintype "passive"))
      (node (ref "SW48") (pin "2") (pinfunction "2_2") (pintype "passive"))
      (node (ref "SW62") (pin "2") (pinfunction "2_2") (pintype "passive"))
      (node (ref "SW76") (pin "2") (pinfunction "2_2") (pintype "passive"))
    )
    (net (code "12") (name "/OUT5_MCU_KEYPAD") (class "Default")
      (node (ref "SW20") (pin "2") (pinfunction "2_2") (pintype "passive"))
      (node (ref "SW35") (pin "2") (pinfunction "2_2") (pintype "passive"))
      (node (ref "SW4") (pin "2") (pinfunction "2_2") (pintype "passive"))
      (node (ref "SW49") (pin "2") (pinfunction "2_2") (pintype "passive"))
      (node (ref "SW63") (pin "2") (pinfunction "2_2") (pintype "passive"))
      (node (ref "SW77") (pin "2") (pinfunction "2_2") (pintype "passive"))
    )
    (net (code "13") (name "/OUT6_MCU_KEYPAD") (class "Default")
      (node (ref "SW21") (pin "2") (pinfunction "2_2") (pintype "passive"))
      (node (ref "SW36") (pin "2") (pinfunction "2_2") (pintype "passive"))
      (node (ref "SW5") (pin "2") (pinfunction "2_2") (pintype "passive"))
      (node (ref "SW50") (pin "2") (pinfunction "2_2") (pintype "passive"))
      (node (ref "SW64") (pin "2") (pinfunction "2_2") (pintype "passive"))
    )
    (net (code "14") (name "/OUT7_MCU_KEYPAD") (class "Default")
      (node (ref "SW22") (pin "2") (pinfunction "2_2") (pintype "passive"))
      (node (ref "SW37") (pin "2") (pinfunction "2_2") (pintype "passive"))
      (node (ref "SW51") (pin "2") (pinfunction "2_2") (pintype "passive"))
      (node (ref "SW6") (pin "2") (pinfunction "2_2") (pintype "passive"))
      (node (ref "SW65") (pin "2") (pinfunction "2_2") (pintype "passive"))
    )
    (net (code "15") (name "/OUT8_MCU_KEYPAD") (class "Default")
      (node (ref "SW23") (pin "2") (pinfunction "2_2") (pintype "passive"))
      (node (ref "SW38") (pin "2") (pinfunction "2_2") (pintype "passive"))
      (node (ref "SW52") (pin "2") (pinfunction "2_2") (pintype "passive"))
      (node (ref "SW66") (pin "2") (pinfunction "2_2") (pintype "passive"))
      (node (ref "SW7") (pin "2") (pinfunction "2_2") (pintype "passive"))
    )
    (net (code "16") (name "/OUT9_MCU_KEYPAD") (class "Default")
      (node (ref "SW24") (pin "2") (pinfunction "2_2") (pintype "passive"))
      (node (ref "SW39") (pin "2") (pinfunction "2_2") (pintype "passive"))
      (node (ref "SW53") (pin "2") (pinfunction "2_2") (pintype "passive"))
      (node (ref "SW67") (pin "2") (pinfunction "2_2") (pintype "passive"))
      (node (ref "SW8") (pin "2") (pinfunction "2_2") (pintype "passive"))
    )
    (net (code "17") (name "/OUT10_MCU_KEYPAD") (class "Default")
      (node (ref "SW25") (pin "2") (pinfunction "2_2") (pintype "passive"))
      (node (ref "SW40") (pin "2") (pinfunction "2_2") (pintype "passive"))
      (node (ref "SW54") (pin "2") (pinfunction "2_2") (pintype "passive"))
      (node (ref "SW68") (pin "2") (pinfunction "2_2") (pintype "passive"))
      (node (ref "SW9") (pin "2") (pinfunction "2_2") (pintype "passive"))
    )
    (net (code "18") (name "/OUT11_MCU_KEYPAD") (class "Default")
      (node (ref "SW10") (pin "2") (pinfunction "2_2") (pintype "passive"))
      (node (ref "SW26") (pin "2") (pinfunction "2_2") (pintype "passive"))
      (node (ref "SW41") (pin "2") (pinfunction "2_2") (pintype "passive"))
      (node (ref "SW55") (pin "2") (pinfunction "2_2") (pintype "passive"))
      (node (ref "SW69") (pin "2") (pinfunction "2_2") (pintype "passive"))
    )
    (net (code "19") (name "/OUT12_MCU_KEYPAD") (class "Default")
      (node (ref "SW11") (pin "2") (pinfunction "2_2") (pintype "passive"))
      (node (ref "SW27") (pin "2") (pinfunction "2_2") (pintype "passive"))
      (node (ref "SW42") (pin "2") (pinfunction "2_2") (pintype "passive"))
      (node (ref "SW56") (pin "2") (pinfunction "2_2") (pintype "passive"))
      (node (ref "SW70") (pin "2") (pinfunction "2_2") (pintype "passive"))
      (node (ref "SW78") (pin "2") (pinfunction "2_2") (pintype "passive"))
    )
    (net (code "20") (name "/OUT13_MCU_KEYPAD") (class "Default")
      (node (ref "SW12") (pin "2") (pinfunction "2_2") (pintype "passive"))
      (node (ref "SW28") (pin "2") (pinfunction "2_2") (pintype "passive"))
      (node (ref "SW43") (pin "2") (pinfunction "2_2") (pintype "passive"))
      (node (ref "SW57") (pin "2") (pinfunction "2_2") (pintype "passive"))
      (node (ref "SW71") (pin "2") (pinfunction "2_2") (pintype "passive"))
      (node (ref "SW79") (pin "2") (pinfunction "2_2") (pintype "passive"))
    )
    (net (code "21") (name "/OUT14_MCU_KEYPAD") (class "Default")
      (node (ref "SW13") (pin "2") (pinfunction "2_2") (pintype "passive"))
      (node (ref "SW29") (pin "2") (pinfunction "2_2") (pintype "passive"))
      (node (ref "SW44") (pin "2") (pinfunction "2_2") (pintype "passive"))
      (node (ref "SW58") (pin "2") (pinfunction "2_2") (pintype "passive"))
      (node (ref "SW80") (pin "2") (pinfunction "2_2") (pintype "passive"))
    )
    (net (code "22") (name "/OUT15_MCU_KEYPAD") (class "Default")
      (node (ref "SW14") (pin "2") (pinfunction "2_2") (pintype "passive"))
      (node (ref "SW30") (pin "2") (pinfunction "2_2") (pintype "passive"))
      (node (ref "SW45") (pin "2") (pinfunction "2_2") (pintype "passive"))
      (node (ref "SW72") (pin "2") (pinfunction "2_2") (pintype "passive"))
      (node (ref "SW81") (pin "2") (pinfunction "2_2") (pintype "passive"))
    )
    (net (code "23") (name "/OUT16_MCU_KEYPAD") (class "Default")
      (node (ref "SW15") (pin "2") (pinfunction "2_2") (pintype "passive"))
      (node (ref "SW73") (pin "2") (pinfunction "2_2") (pintype "passive"))
      (node (ref "SW82") (pin "2") (pinfunction "2_2") (pintype "passive"))
    )
    (net (code "24") (name "GND") (class "Default")
      (node (ref "C1") (pin "2") (pinfunction "2_2") (pintype "passive"))
      (node (ref "C2") (pin "2") (pinfunction "2_2") (pintype "passive"))
      (node (ref "C3") (pin "2") (pinfunction "2_2") (pintype "passive"))
      (node (ref "C4") (pin "2") (pinfunction "2_2") (pintype "passive"))
      (node (ref "C5") (pin "2") (pinfunction "2_2") (pintype "passive"))
      (node (ref "C6") (pin "2") (pinfunction "2_2") (pintype "passive"))
      (node (ref "C7") (pin "2") (pinfunction "2_2") (pintype "passive"))
      (node (ref "SW83") (pin "2") (pinfunction "2_2") (pintype "passive"))
    )
    (net (code "25") (name "Net-(D1-PadA)") (class "Default")
      (node (ref "D1") (pin "A") (pinfunction "A_A") (pintype "passive"))
      (node (ref "SW1") (pin "1") (pinfunction "1_1") (pintype "passive"))
    )
    (net (code "26") (name "Net-(D2-PadA)") (class "Default")
      (node (ref "D2") (pin "A") (pinfunction "A_A") (pintype "passive"))
      (node (ref "SW2") (pin "1") (pinfunction "1_1") (pintype "passive"))
    )
    (net (code "27") (name "Net-(D3-PadA)") (class "Default")
      (node (ref "D3") (pin "A") (pinfunction "A_A") (pintype "passive"))
      (node (ref "SW3") (pin "1") (pinfunction "1_1") (pintype "passive"))
    )
    (net (code "28") (name "Net-(D4-PadA)") (class "Default")
      (node (ref "D4") (pin "A") (pinfunction "A_A") (pintype "passive"))
      (node (ref "SW4") (pin "1") (pinfunction "1_1") (pintype "passive"))
    )
    (net (code "29") (name "Net-(D5-PadA)") (class "Default")
      (node (ref "D5") (pin "A") (pinfunction "A_A") (pintype "passive"))
      (node (ref "SW5") (pin "1") (pinfunction "1_1") (pintype "passive"))
    )
    (net (code "30") (name "Net-(D6-PadA)") (class "Default")
      (node (ref "D6") (pin "A") (pinfunction "A_A") (pintype "passive"))
      (node (ref "SW6") (pin "1") (pinfunction "1_1") (pintype "passive"))
    )
    (net (code "31") (name "Net-(D7-PadA)") (class "Default")
      (node (ref "D7") (pin "A") (pinfunction "A_A") (pintype "passive"))
      (node (ref "SW7") (pin "1") (pinfunction "1_1") (pintype "passive"))
    )
    (net (code "32") (name "Net-(D8-PadA)") (class "Default")
      (node (ref "D8") (pin "A") (pinfunction "A_A") (pintype "passive"))
      (node (ref "SW8") (pin "1") (pinfunction "1_1") (pintype "passive"))
    )
    (net (code "33") (name "Net-(D9-PadA)") (class "Default")
      (node (ref "D9") (pin "A") (pinfunction "A_A") (pintype "passive"))
      (node (ref "SW9") (pin "1") (pinfunction "1_1") (pintype "passive"))
    )
    (net (code "34") (name "Net-(D10-PadA)") (class "Default")
      (node (ref "D10") (pin "A") (pinfunction "A_A") (pintype "passive"))
      (node (ref "SW10") (pin "1") (pinfunction "1_1") (pintype "passive"))
    )
    (net (code "35") (name "Net-(D11-PadA)") (class "Default")
      (node (ref "D11") (pin "A") (pinfunction "A_A") (pintype "passive"))
      (node (ref "SW11") (pin "1") (pinfunction "1_1") (pintype "passive"))
    )
    (net (code "36") (name "Net-(D12-PadA)") (class "Default")
      (node (ref "D12") (pin "A") (pinfunction "A_A") (pintype "passive"))
      (node (ref "SW12") (pin "1") (pinfunction "1_1") (pintype "passive"))
    )
    (net (code "37") (name "Net-(D13-PadA)") (class "Default")
      (node (ref "D13") (pin "A") (pinfunction "A_A") (pintype "passive"))
      (node (ref "SW13") (pin "1") (pinfunction "1_1") (pintype "passive"))
    )
    (net (code "38") (name "Net-(D14-PadA)") (class "Default")
      (node (ref "D14") (pin "A") (pinfunction "A_A") (pintype "passive"))
      (node (ref "SW14") (pin "1") (pinfunction "1_1") (pintype "passive"))
    )
    (net (code "39") (name "Net-(D15-PadA)") (class "Default")
      (node (ref "D15") (pin "A") (pinfunction "A_A") (pintype "passive"))
      (node (ref "SW15") (pin "1") (pinfunction "1_1") (pintype "passive"))
    )
    (net (code "40") (name "Net-(D16-PadA)") (class "Default")
      (node (ref "D16") (pin "A") (pinfunction "A_A") (pintype "passive"))
      (node (ref "SW16") (pin "1") (pinfunction "1_1") (pintype "passive"))
    )
    (net (code "41") (name "Net-(D17-PadA)") (class "Default")
      (node (ref "D17") (pin "A") (pinfunction "A_A") (pintype "passive"))
      (node (ref "SW17") (pin "1") (pinfunction "1_1") (pintype "passive"))
    )
    (net (code "42") (name "Net-(D18-PadA)") (class "Default")
      (node (ref "D18") (pin "A") (pinfunction "A_A") (pintype "passive"))
      (node (ref "SW18") (pin "1") (pinfunction "1_1") (pintype "passive"))
    )
    (net (code "43") (name "Net-(D19-PadA)") (class "Default")
      (node (ref "D19") (pin "A") (pinfunction "A_A") (pintype "passive"))
      (node (ref "SW19") (pin "1") (pinfunction "1_1") (pintype "passive"))
    )
    (net (code "44") (name "Net-(D20-PadA)") (class "Default")
      (node (ref "D20") (pin "A") (pinfunction "A_A") (pintype "passive"))
      (node (ref "SW20") (pin "1") (pinfunction "1_1") (pintype "passive"))
    )
    (net (code "45") (name "Net-(D21-PadA)") (class "Default")
      (node (ref "D21") (pin "A") (pinfunction "A_A") (pintype "passive"))
      (node (ref "SW21") (pin "1") (pinfunction "1_1") (pintype "passive"))
    )
    (net (code "46") (name "Net-(D22-PadA)") (class "Default")
      (node (ref "D22") (pin "A") (pinfunction "A_A") (pintype "passive"))
      (node (ref "SW22") (pin "1") (pinfunction "1_1") (pintype "passive"))
    )
    (net (code "47") (name "Net-(D23-PadA)") (class "Default")
      (node (ref "D23") (pin "A") (pinfunction "A_A") (pintype "passive"))
      (node (ref "SW23") (pin "1") (pinfunction "1_1") (pintype "passive"))
    )
    (net (code "48") (name "Net-(D24-PadA)") (class "Default")
      (node (ref "D24") (pin "A") (pinfunction "A_A") (pintype "passive"))
      (node (ref "SW24") (pin "1") (pinfunction "1_1") (pintype "passive"))
    )
    (net (code "49") (name "Net-(D25-PadA)") (class "Default")
      (node (ref "D25") (pin "A") (pinfunction "A_A") (pintype "passive"))
      (node (ref "SW25") (pin "1") (pinfunction "1_1") (pintype "passive"))
    )
    (net (code "50") (name "Net-(D26-PadA)") (class "Default")
      (node (ref "D26") (pin "A") (pinfunction "A_A") (pintype "passive"))
      (node (ref "SW26") (pin "1") (pinfunction "1_1") (pintype "passive"))
    )
    (net (code "51") (name "Net-(D27-PadA)") (class "Default")
      (node (ref "D27") (pin "A") (pinfunction "A_A") (pintype "passive"))
      (node (ref "SW27") (pin "1") (pinfunction "1_1") (pintype "passive"))
    )
    (net (code "52") (name "Net-(D28-PadA)") (class "Default")
      (node (ref "D28") (pin "A") (pinfunction "A_A") (pintype "passive"))
      (node (ref "SW28") (pin "1") (pinfunction "1_1") (pintype "passive"))
    )
    (net (code "53") (name "Net-(D29-PadA)") (class "Default")
      (node (ref "D29") (pin "A") (pinfunction "A_A") (pintype "passive"))
      (node (ref "SW29") (pin "1") (pinfunction "1_1") (pintype "passive"))
    )
    (net (code "54") (name "Net-(D30-PadA)") (class "Default")
      (node (ref "D30") (pin "A") (pinfunction "A_A") (pintype "passive"))
      (node (ref "SW30") (pin "1") (pinfunction "1_1") (pintype "passive"))
    )
    (net (code "55") (name "Net-(D31-PadA)") (class "Default")
      (node (ref "D31") (pin "A") (pinfunction "A_A") (pintype "passive"))
      (node (ref "SW31") (pin "1") (pinfunction "1_1") (pintype "passive"))
    )
    (net (code "56") (name "Net-(D32-PadA)") (class "Default")
      (node (ref "D32") (pin "A") (pinfunction "A_A") (pintype "passive"))
      (node (ref "SW32") (pin "1") (pinfunction "1_1") (pintype "passive"))
    )
    (net (code "57") (name "Net-(D33-PadA)") (class "Default")
      (node (ref "D33") (pin "A") (pinfunction "A_A") (pintype "passive"))
      (node (ref "SW33") (pin "1") (pinfunction "1_1") (pintype "passive"))
    )
    (net (code "58") (name "Net-(D34-PadA)") (class "Default")
      (node (ref "D34") (pin "A") (pinfunction "A_A") (pintype "passive"))
      (node (ref "SW34") (pin "1") (pinfunction "1_1") (pintype "passive"))
    )
    (net (code "59") (name "Net-(D35-PadA)") (class "Default")
      (node (ref "D35") (pin "A") (pinfunction "A_A") (pintype "passive"))
      (node (ref "SW35") (pin "1") (pinfunction "1_1") (pintype "passive"))
    )
    (net (code "60") (name "Net-(D36-PadA)") (class "Default")
      (node (ref "D36") (pin "A") (pinfunction "A_A") (pintype "passive"))
      (node (ref "SW36") (pin "1") (pinfunction "1_1") (pintype "passive"))
    )
    (net (code "61") (name "Net-(D37-PadA)") (class "Default")
      (node (ref "D37") (pin "A") (pinfunction "A_A") (pintype "passive"))
      (node (ref "SW37") (pin "1") (pinfunction "1_1") (pintype "passive"))
    )
    (net (code "62") (name "Net-(D38-PadA)") (class "Default")
      (node (ref "D38") (pin "A") (pinfunction "A_A") (pintype "passive"))
      (node (ref "SW38") (pin "1") (pinfunction "1_1") (pintype "passive"))
    )
    (net (code "63") (name "Net-(D39-PadA)") (class "Default")
      (node (ref "D39") (pin "A") (pinfunction "A_A") (pintype "passive"))
      (node (ref "SW39") (pin "1") (pinfunction "1_1") (pintype "passive"))
    )
    (net (code "64") (name "Net-(D40-PadA)") (class "Default")
      (node (ref "D40") (pin "A") (pinfunction "A_A") (pintype "passive"))
      (node (ref "SW40") (pin "1") (pinfunction "1_1") (pintype "passive"))
    )
    (net (code "65") (name "Net-(D41-PadA)") (class "Default")
      (node (ref "D41") (pin "A") (pinfunction "A_A") (pintype "passive"))
      (node (ref "SW41") (pin "1") (pinfunction "1_1") (pintype "passive"))
    )
    (net (code "66") (name "Net-(D42-PadA)") (class "Default")
      (node (ref "D42") (pin "A") (pinfunction "A_A") (pintype "passive"))
      (node (ref "SW42") (pin "1") (pinfunction "1_1") (pintype "passive"))
    )
    (net (code "67") (name "Net-(D43-PadA)") (class "Default")
      (node (ref "D43") (pin "A") (pinfunction "A_A") (pintype "passive"))
      (node (ref "SW43") (pin "1") (pinfunction "1_1") (pintype "passive"))
    )
    (net (code "68") (name "Net-(D44-PadA)") (class "Default")
      (node (ref "D44") (pin "A") (pinfunction "A_A") (pintype "passive"))
      (node (ref "SW44") (pin "1") (pinfunction "1_1") (pintype "passive"))
    )
    (net (code "69") (name "Net-(D45-PadA)") (class "Default")
      (node (ref "D45") (pin "A") (pinfunction "A_A") (pintype "passive"))
      (node (ref "SW45") (pin "1") (pinfunction "1_1") (pintype "passive"))
    )
    (net (code "70") (name "Net-(D46-PadA)") (class "Default")
      (node (ref "D46") (pin "A") (pinfunction "A_A") (pintype "passive"))
      (node (ref "SW46") (pin "1") (pinfunction "1_1") (pintype "passive"))
    )
    (net (code "71") (name "Net-(D47-PadA)") (class "Default")
      (node (ref "D47") (pin "A") (pinfunction "A_A") (pintype "passive"))
      (node (ref "SW59") (pin "1") (pinfunction "1_1") (pintype "passive"))
    )
    (net (code "72") (name "Net-(D48-PadA)") (class "Default")
      (node (ref "D48") (pin "A") (pinfunction "A_A") (pintype "passive"))
      (node (ref "SW47") (pin "1") (pinfunction "1_1") (pintype "passive"))
    )
    (net (code "73") (name "Net-(D49-PadA)") (class "Default")
      (node (ref "D49") (pin "A") (pinfunction "A_A") (pintype "passive"))
      (node (ref "SW48") (pin "1") (pinfunction "1_1") (pintype "passive"))
    )
    (net (code "74") (name "Net-(D50-PadA)") (class "Default")
      (node (ref "D50") (pin "A") (pinfunction "A_A") (pintype "passive"))
      (node (ref "SW49") (pin "1") (pinfunction "1_1") (pintype "passive"))
    )
    (net (code "75") (name "Net-(D51-PadA)") (class "Default")
      (node (ref "D51") (pin "A") (pinfunction "A_A") (pintype "passive"))
      (node (ref "SW50") (pin "1") (pinfunction "1_1") (pintype "passive"))
    )
    (net (code "76") (name "Net-(D52-PadA)") (class "Default")
      (node (ref "D52") (pin "A") (pinfunction "A_A") (pintype "passive"))
      (node (ref "SW51") (pin "1") (pinfunction "1_1") (pintype "passive"))
    )
    (net (code "77") (name "Net-(D53-PadA)") (class "Default")
      (node (ref "D53") (pin "A") (pinfunction "A_A") (pintype "passive"))
      (node (ref "SW52") (pin "1") (pinfunction "1_1") (pintype "passive"))
    )
    (net (code "78") (name "Net-(D54-PadA)") (class "Default")
      (node (ref "D54") (pin "A") (pinfunction "A_A") (pintype "passive"))
      (node (ref "SW53") (pin "1") (pinfunction "1_1") (pintype "passive"))
    )
    (net (code "79") (name "Net-(D55-PadA)") (class "Default")
      (node (ref "D55") (pin "A") (pinfunction "A_A") (pintype "passive"))
      (node (ref "SW54") (pin "1") (pinfunction "1_1") (pintype "passive"))
    )
    (net (code "80") (name "Net-(D56-PadA)") (class "Default")
      (node (ref "D56") (pin "A") (pinfunction "A_A") (pintype "passive"))
      (node (ref "SW55") (pin "1") (pinfunction "1_1") (pintype "passive"))
    )
    (net (code "81") (name "Net-(D57-PadA)") (class "Default")
      (node (ref "D57") (pin "A") (pinfunction "A_A") (pintype "passive"))
      (node (ref "SW56") (pin "1") (pinfunction "1_1") (pintype "passive"))
    )
    (net (code "82") (name "Net-(D58-PadA)") (class "Default")
      (node (ref "D58") (pin "A") (pinfunction "A_A") (pintype "passive"))
      (node (ref "SW57") (pin "1") (pinfunction "1_1") (pintype "passive"))
    )
    (net (code "83") (name "Net-(D59-PadA)") (class "Default")
      (node (ref "D59") (pin "A") (pinfunction "A_A") (pintype "passive"))
      (node (ref "SW58") (pin "1") (pinfunction "1_1") (pintype "passive"))
    )
    (net (code "84") (name "Net-(D60-PadA)") (class "Default")
      (node (ref "D60") (pin "A") (pinfunction "A_A") (pintype "passive"))
      (node (ref "SW60") (pin "1") (pinfunction "1_1") (pintype "passive"))
    )
    (net (code "85") (name "Net-(D61-PadA)") (class "Default")
      (node (ref "D61") (pin "A") (pinfunction "A_A") (pintype "passive"))
      (node (ref "SW61") (pin "1") (pinfunction "1_1") (pintype "passive"))
    )
    (net (code "86") (name "Net-(D62-PadA)") (class "Default")
      (node (ref "D62") (pin "A") (pinfunction "A_A") (pintype "passive"))
      (node (ref "SW62") (pin "1") (pinfunction "1_1") (pintype "passive"))
    )
    (net (code "87") (name "Net-(D63-PadA)") (class "Default")
      (node (ref "D63") (pin "A") (pinfunction "A_A") (pintype "passive"))
      (node (ref "SW63") (pin "1") (pinfunction "1_1") (pintype "passive"))
    )
    (net (code "88") (name "Net-(D64-PadA)") (class "Default")
      (node (ref "D64") (pin "A") (pinfunction "A_A") (pintype "passive"))
      (node (ref "SW64") (pin "1") (pinfunction "1_1") (pintype "passive"))
    )
    (net (code "89") (name "Net-(D65-PadA)") (class "Default")
      (node (ref "D65") (pin "A") (pinfunction "A_A") (pintype "passive"))
      (node (ref "SW65") (pin "1") (pinfunction "1_1") (pintype "passive"))
    )
    (net (code "90") (name "Net-(D66-PadA)") (class "Default")
      (node (ref "D66") (pin "A") (pinfunction "A_A") (pintype "passive"))
      (node (ref "SW66") (pin "1") (pinfunction "1_1") (pintype "passive"))
    )
    (net (code "91") (name "Net-(D67-PadA)") (class "Default")
      (node (ref "D67") (pin "A") (pinfunction "A_A") (pintype "passive"))
      (node (ref "SW67") (pin "1") (pinfunction "1_1") (pintype "passive"))
    )
    (net (code "92") (name "Net-(D68-PadA)") (class "Default")
      (node (ref "D68") (pin "A") (pinfunction "A_A") (pintype "passive"))
      (node (ref "SW68") (pin "1") (pinfunction "1_1") (pintype "passive"))
    )
    (net (code "93") (name "Net-(D69-PadA)") (class "Default")
      (node (ref "D69") (pin "A") (pinfunction "A_A") (pintype "passive"))
      (node (ref "SW69") (pin "1") (pinfunction "1_1") (pintype "passive"))
    )
    (net (code "94") (name "Net-(D70-PadA)") (class "Default")
      (node (ref "D70") (pin "A") (pinfunction "A_A") (pintype "passive"))
      (node (ref "SW70") (pin "1") (pinfunction "1_1") (pintype "passive"))
    )
    (net (code "95") (name "Net-(D71-PadA)") (class "Default")
      (node (ref "D71") (pin "A") (pinfunction "A_A") (pintype "passive"))
      (node (ref "SW71") (pin "1") (pinfunction "1_1") (pintype "passive"))
    )
    (net (code "96") (name "Net-(D72-PadA)") (class "Default")
      (node (ref "D72") (pin "A") (pinfunction "A_A") (pintype "passive"))
      (node (ref "SW72") (pin "1") (pinfunction "1_1") (pintype "passive"))
    )
    (net (code "97") (name "Net-(D73-PadA)") (class "Default")
      (node (ref "D73") (pin "A") (pinfunction "A_A") (pintype "passive"))
      (node (ref "SW73") (pin "1") (pinfunction "1_1") (pintype "passive"))
    )
    (net (code "98") (name "Net-(D74-PadA)") (class "Default")
      (node (ref "D74") (pin "A") (pinfunction "A_A") (pintype "passive"))
      (node (ref "SW74") (pin "1") (pinfunction "1_1") (pintype "passive"))
    )
    (net (code "99") (name "Net-(D75-PadA)") (class "Default")
      (node (ref "D75") (pin "A") (pinfunction "A_A") (pintype "passive"))
      (node (ref "SW75") (pin "1") (pinfunction "1_1") (pintype "passive"))
    )
    (net (code "100") (name "Net-(D76-PadA)") (class "Default")
      (node (ref "D76") (pin "A") (pinfunction "A_A") (pintype "passive"))
      (node (ref "SW76") (pin "1") (pinfunction "1_1") (pintype "passive"))
    )
    (net (code "101") (name "Net-(D77-PadA)") (class "Default")
      (node (ref "D77") (pin "A") (pinfunction "A_A") (pintype "passive"))
      (node (ref "SW77") (pin "1") (pinfunction "1_1") (pintype "passive"))
    )
    (net (code "102") (name "Net-(D78-PadA)") (class "Default")
      (node (ref "D78") (pin "A") (pinfunction "A_A") (pintype "passive"))
      (node (ref "SW78") (pin "1") (pinfunction "1_1") (pintype "passive"))
    )
    (net (code "103") (name "Net-(D79-PadA)") (class "Default")
      (node (ref "D79") (pin "A") (pinfunction "A_A") (pintype "passive"))
      (node (ref "SW79") (pin "1") (pinfunction "1_1") (pintype "passive"))
    )
    (net (code "104") (name "Net-(D80-PadA)") (class "Default")
      (node (ref "D80") (pin "A") (pinfunction "A_A") (pintype "passive"))
      (node (ref "SW80") (pin "1") (pinfunction "1_1") (pintype "passive"))
    )
    (net (code "105") (name "Net-(D81-PadA)") (class "Default")
      (node (ref "D81") (pin "A") (pinfunction "A_A") (pintype "passive"))
      (node (ref "SW81") (pin "1") (pinfunction "1_1") (pintype "passive"))
    )
    (net (code "106") (name "Net-(D82-PadA)") (class "Default")
      (node (ref "D82") (pin "A") (pinfunction "A_A") (pintype "passive"))
      (node (ref "SW82") (pin "1") (pinfunction "1_1") (pintype "passive"))
    )
  )
)
